# FuzzyNavel.net
KiCad netlist of a schematic drawn in EAGLE
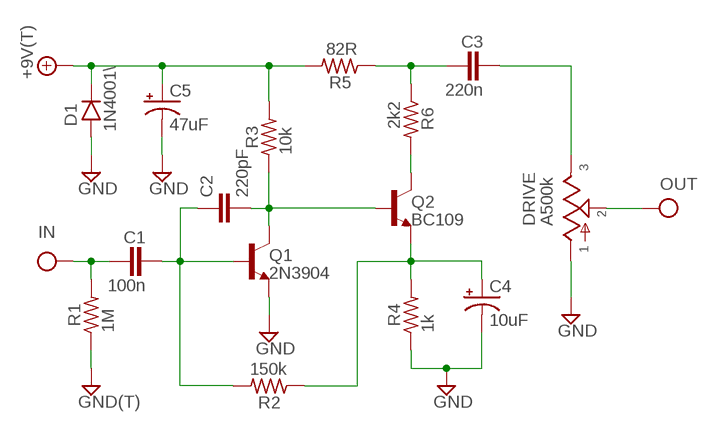
[diagram p0: schematic, sheet 1]

(export (version "E")
  (design (tool "Eeschema 10.0.6"))
  (components
    (comp (ref "+9V")
      (value "+9V(T)")
      (footprint "eagle-import:SQUARE")
      (libsource (lib "eagle-import") (part "+9V(T)"))
    )
    (comp (ref "C1")
      (value "100n")
      (footprint "eagle-import:072X025")
      (libsource (lib "eagle-import") (part "072X0252"))
    )
    (comp (ref "C2")
      (value "220pF")
      (footprint "eagle-import:050X030_050_1")
      (libsource (lib "eagle-import") (part "050X030_0501"))
    )
    (comp (ref "C3")
      (value "220n")
      (footprint "eagle-import:072X035")
      (libsource (lib "eagle-import") (part "072X0352"))
    )
    (comp (ref "C4")
      (value "10uF")
      (footprint "eagle-import:050_020_1")
      (libsource (lib "eagle-import") (part "0501"))
    )
    (comp (ref "C5")
      (value "47uF")
      (footprint "eagle-import:050_020_1")
      (libsource (lib "eagle-import") (part "0501"))
    )
    (comp (ref "D1")
      (value "1N4001\\")
      (footprint "eagle-import:DO41-2")
      (libsource (lib "eagle-import") (part "1N400X.2"))
    )
    (comp (ref "DRIVE")
      (value "A500k")
      (footprint "eagle-import:16MM_PCB_PADS")
      (libsource (lib "eagle-import") (part "POT16MM_PCB_PADS"))
    )
    (comp (ref "GND")
      (value "GND(T)")
      (footprint "eagle-import:SQUARE")
      (libsource (lib "eagle-import") (part "GND(T)"))
    )
    (comp (ref "IN")
      (value "IN(T)")
      (footprint "eagle-import:SQUARE")
      (libsource (lib "eagle-import") (part "IN(T)"))
    )
    (comp (ref "OUT")
      (value "OUT(T)")
      (footprint "eagle-import:SQUARE")
      (libsource (lib "eagle-import") (part "OUT(T)"))
    )
    (comp (ref "Q1")
      (value "2N3904")
      (footprint "eagle-import:TO92-")
      (libsource (lib "eagle-import") (part "2N3904"))
    )
    (comp (ref "Q2")
      (value "BC109")
      (footprint "eagle-import:TO92-")
      (libsource (lib "eagle-import") (part "2N3904"))
    )
    (comp (ref "R1")
      (value "1M")
      (footprint "eagle-import:R0207_3")
      (libsource (lib "eagle-import") (part "6MM.3"))
    )
    (comp (ref "R2")
      (value "150k")
      (footprint "eagle-import:R0207_3")
      (libsource (lib "eagle-import") (part "6MM.3"))
    )
    (comp (ref "R3")
      (value "10k")
      (footprint "eagle-import:R0207_3")
      (libsource (lib "eagle-import") (part "6MM.3"))
    )
    (comp (ref "R4")
      (value "1k")
      (footprint "eagle-import:R0207_3")
      (libsource (lib "eagle-import") (part "6MM.3"))
    )
    (comp (ref "R5")
      (value "82R")
      (footprint "eagle-import:R0207_3")
      (libsource (lib "eagle-import") (part "6MM.3"))
    )
    (comp (ref "R6")
      (value "2k2")
      (footprint "eagle-import:R0207_3")
      (libsource (lib "eagle-import") (part "6MM.3"))
    )
  )
  (nets
    (net (code "1") (name "+9V(T)") (class "Default")
      (node (ref "+9V") (pin "1") (pinfunction "+9V_1") (pintype "power_in"))
      (node (ref "C5") (pin "+") (pinfunction "+_+") (pintype "passive"))
      (node (ref "D1") (pin "C") (pinfunction "C_C") (pintype "passive"))
      (node (ref "R3") (pin "2") (pinfunction "2_2") (pintype "passive"))
      (node (ref "R5") (pin "2") (pinfunction "2_2") (pintype "passive"))
    )
    (net (code "2") (name "GND") (class "Default")
      (node (ref "C4") (pin "-") (pinfunction "-_-") (pintype "passive"))
      (node (ref "C5") (pin "-") (pinfunction "-_-") (pintype "passive"))
      (node (ref "D1") (pin "A") (pinfunction "A_A") (pintype "passive"))
      (node (ref "DRIVE") (pin "1") (pinfunction "1_1") (pintype "passive"))
      (node (ref "GND") (pin "1") (pinfunction "GND_1") (pintype "power_in"))
      (node (ref "Q1") (pin "3") (pinfunction "E_3") (pintype "passive"))
      (node (ref "R1") (pin "1") (pinfunction "1_1") (pintype "passive"))
      (node (ref "R4") (pin "1") (pinfunction "1_1") (pintype "passive"))
    )
    (net (code "3") (name "IN(T)") (class "Default")
      (node (ref "C1") (pin "1") (pinfunction "1_1") (pintype "passive"))
      (node (ref "IN") (pin "1") (pinfunction "IN_1") (pintype "power_in"))
      (node (ref "R1") (pin "2") (pinfunction "2_2") (pintype "passive"))
    )
    (net (code "4") (name "Net-(C3-Pad1)") (class "Default")
      (node (ref "C3") (pin "1") (pinfunction "1_1") (pintype "passive"))
      (node (ref "R5") (pin "1") (pinfunction "1_1") (pintype "passive"))
      (node (ref "R6") (pin "1") (pinfunction "1_1") (pintype "passive"))
    )
    (net (code "5") (name "Net-(C3-Pad2)") (class "Default")
      (node (ref "C3") (pin "2") (pinfunction "2_2") (pintype "passive"))
      (node (ref "DRIVE") (pin "3") (pinfunction "3_3") (pintype "passive"))
    )
    (net (code "6") (name "Net-(Q1-B)") (class "Default")
      (node (ref "C1") (pin "2") (pinfunction "2_2") (pintype "passive"))
      (node (ref "C2") (pin "1") (pinfunction "1_1") (pintype "passive"))
      (node (ref "Q1") (pin "2") (pinfunction "B_2") (pintype "passive"))
      (node (ref "R2") (pin "2") (pinfunction "2_2") (pintype "passive"))
    )
    (net (code "7") (name "Net-(Q1-C)") (class "Default")
      (node (ref "C2") (pin "2") (pinfunction "2_2") (pintype "passive"))
      (node (ref "Q1") (pin "1") (pinfunction "C_1") (pintype "passive"))
      (node (ref "Q2") (pin "2") (pinfunction "B_2") (pintype "passive"))
      (node (ref "R3") (pin "1") (pinfunction "1_1") (pintype "passive"))
    )
    (net (code "8") (name "Net-(Q2-C)") (class "Default")
      (node (ref "Q2") (pin "1") (pinfunction "C_1") (pintype "passive"))
      (node (ref "R6") (pin "2") (pinfunction "2_2") (pintype "passive"))
    )
    (net (code "9") (name "Net-(Q2-E)") (class "Default")
      (node (ref "C4") (pin "+") (pinfunction "+_+") (pintype "passive"))
      (node (ref "Q2") (pin "3") (pinfunction "E_3") (pintype "passive"))
      (node (ref "R2") (pin "1") (pinfunction "1_1") (pintype "passive"))
      (node (ref "R4") (pin "2") (pinfunction "2_2") (pintype "passive"))
    )
    (net (code "10") (name "OUT(T)") (class "Default")
      (node (ref "DRIVE") (pin "2") (pinfunction "2_2") (pintype "passive"))
      (node (ref "OUT") (pin "1") (pinfunction "OUT_1") (pintype "power_in"))
    )
  )
)
